# dual-relay-a-3.net
KiCad netlist of a schematic drawn in EAGLE
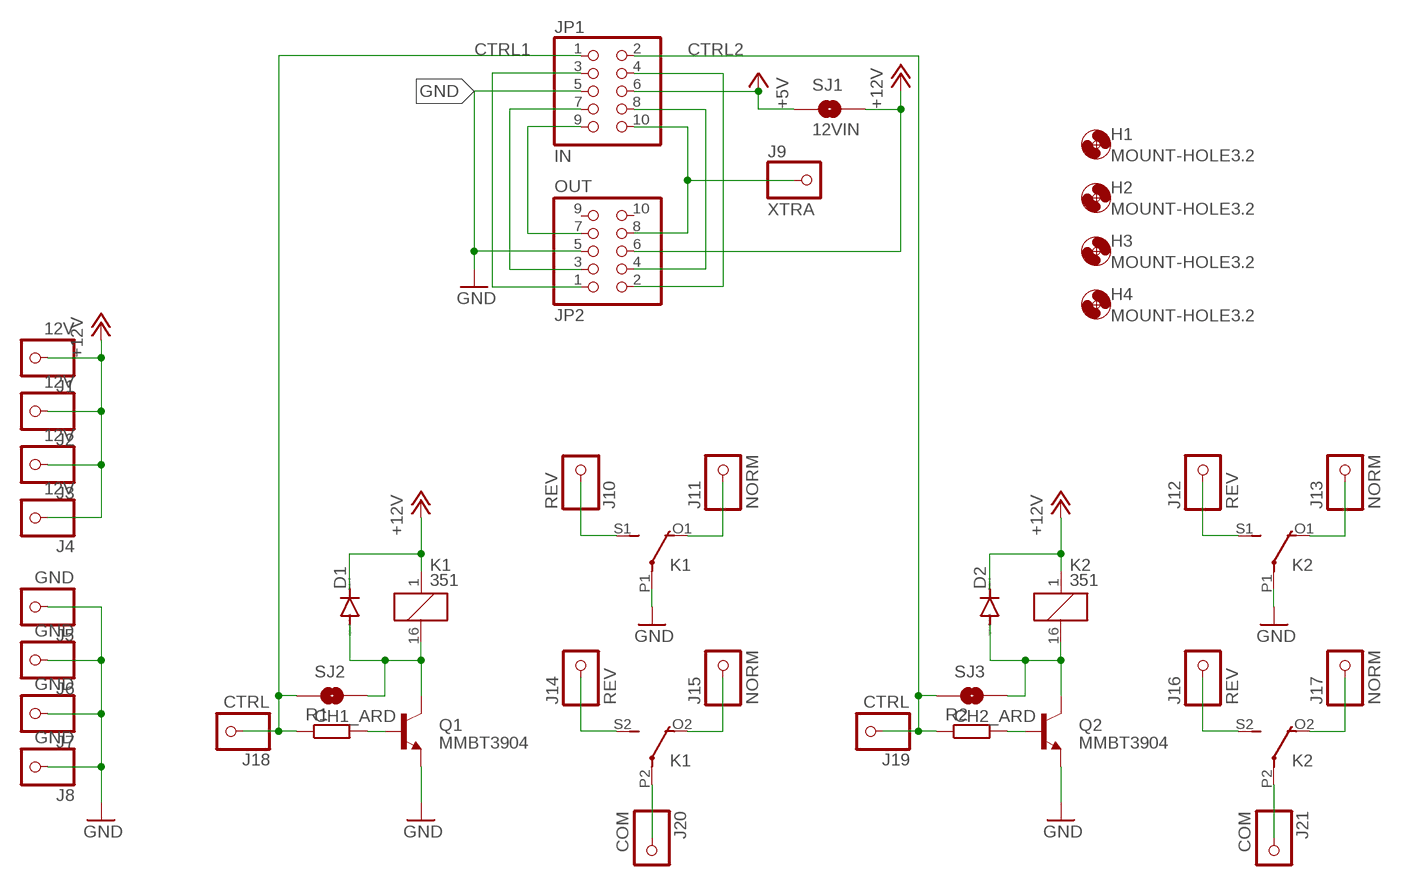
[diagram p0: schematic, sheet 1]

(export (version "E")
  (design (tool "Eeschema 10.0.6"))
  (components
    (comp (ref "D1")
      (value "DIODE-MINIMELF")
      (footprint "eagle-import:MINIMELF")
      (libsource (lib "eagle-import") (part "DIODE-MINIMELF"))
    )
    (comp (ref "D2")
      (value "DIODE-MINIMELF")
      (footprint "eagle-import:MINIMELF")
      (libsource (lib "eagle-import") (part "DIODE-MINIMELF"))
    )
    (comp (ref "H1")
      (value "MOUNT-HOLE3.2")
      (footprint "eagle-import:3,2")
      (libsource (lib "eagle-import") (part "MOUNT-HOLE3.2"))
    )
    (comp (ref "H2")
      (value "MOUNT-HOLE3.2")
      (footprint "eagle-import:3,2")
      (libsource (lib "eagle-import") (part "MOUNT-HOLE3.2"))
    )
    (comp (ref "H3")
      (value "MOUNT-HOLE3.2")
      (footprint "eagle-import:3,2")
      (libsource (lib "eagle-import") (part "MOUNT-HOLE3.2"))
    )
    (comp (ref "H4")
      (value "MOUNT-HOLE3.2")
      (footprint "eagle-import:3,2")
      (libsource (lib "eagle-import") (part "MOUNT-HOLE3.2"))
    )
    (comp (ref "J1")
      (value "12V")
      (footprint "eagle-import:LARGE-SOLDERPAD")
      (libsource (lib "eagle-import") (part "LARGE-SOLDERPAD"))
    )
    (comp (ref "J2")
      (value "12V")
      (footprint "eagle-import:LARGE-SOLDERPAD")
      (libsource (lib "eagle-import") (part "LARGE-SOLDERPAD"))
    )
    (comp (ref "J3")
      (value "12V")
      (footprint "eagle-import:LARGE-SOLDERPAD")
      (libsource (lib "eagle-import") (part "LARGE-SOLDERPAD"))
    )
    (comp (ref "J4")
      (value "12V")
      (footprint "eagle-import:LARGE-SOLDERPAD")
      (libsource (lib "eagle-import") (part "LARGE-SOLDERPAD"))
    )
    (comp (ref "J5")
      (value "GND")
      (footprint "eagle-import:LARGE-SOLDERPAD")
      (libsource (lib "eagle-import") (part "LARGE-SOLDERPAD"))
    )
    (comp (ref "J6")
      (value "GND")
      (footprint "eagle-import:LARGE-SOLDERPAD")
      (libsource (lib "eagle-import") (part "LARGE-SOLDERPAD"))
    )
    (comp (ref "J7")
      (value "GND")
      (footprint "eagle-import:LARGE-SOLDERPAD")
      (libsource (lib "eagle-import") (part "LARGE-SOLDERPAD"))
    )
    (comp (ref "J8")
      (value "GND")
      (footprint "eagle-import:LARGE-SOLDERPAD")
      (libsource (lib "eagle-import") (part "LARGE-SOLDERPAD"))
    )
    (comp (ref "J9")
      (value "XTRA")
      (footprint "eagle-import:LARGE-SOLDERPAD")
      (libsource (lib "eagle-import") (part "LARGE-SOLDERPAD"))
    )
    (comp (ref "J10")
      (value "REV")
      (footprint "eagle-import:LARGE-SOLDERPAD")
      (libsource (lib "eagle-import") (part "LARGE-SOLDERPAD"))
    )
    (comp (ref "J11")
      (value "NORM")
      (footprint "eagle-import:LARGE-SOLDERPAD")
      (libsource (lib "eagle-import") (part "LARGE-SOLDERPAD"))
    )
    (comp (ref "J12")
      (value "REV")
      (footprint "eagle-import:LARGE-SOLDERPAD")
      (libsource (lib "eagle-import") (part "LARGE-SOLDERPAD"))
    )
    (comp (ref "J13")
      (value "NORM")
      (footprint "eagle-import:LARGE-SOLDERPAD")
      (libsource (lib "eagle-import") (part "LARGE-SOLDERPAD"))
    )
    (comp (ref "J14")
      (value "REV")
      (footprint "eagle-import:LARGE-SOLDERPAD")
      (libsource (lib "eagle-import") (part "LARGE-SOLDERPAD"))
    )
    (comp (ref "J15")
      (value "NORM")
      (footprint "eagle-import:LARGE-SOLDERPAD")
      (libsource (lib "eagle-import") (part "LARGE-SOLDERPAD"))
    )
    (comp (ref "J16")
      (value "REV")
      (footprint "eagle-import:LARGE-SOLDERPAD")
      (libsource (lib "eagle-import") (part "LARGE-SOLDERPAD"))
    )
    (comp (ref "J17")
      (value "NORM")
      (footprint "eagle-import:LARGE-SOLDERPAD")
      (libsource (lib "eagle-import") (part "LARGE-SOLDERPAD"))
    )
    (comp (ref "J18")
      (value "CTRL")
      (footprint "eagle-import:LARGE-SOLDERPAD")
      (libsource (lib "eagle-import") (part "LARGE-SOLDERPAD"))
    )
    (comp (ref "J19")
      (value "CTRL")
      (footprint "eagle-import:LARGE-SOLDERPAD")
      (libsource (lib "eagle-import") (part "LARGE-SOLDERPAD"))
    )
    (comp (ref "J20")
      (value "COM")
      (footprint "eagle-import:LARGE-SOLDERPAD")
      (libsource (lib "eagle-import") (part "LARGE-SOLDERPAD"))
    )
    (comp (ref "J21")
      (value "COM")
      (footprint "eagle-import:LARGE-SOLDERPAD")
      (libsource (lib "eagle-import") (part "LARGE-SOLDERPAD"))
    )
    (comp (ref "JP1")
      (value "IN")
      (footprint "eagle-import:CON10M")
      (libsource (lib "eagle-import") (part "PINHD-2X5CN"))
    )
    (comp (ref "JP2")
      (value "OUT")
      (footprint "eagle-import:CON10M")
      (libsource (lib "eagle-import") (part "PINHD-2X5CN"))
    )
    (comp (ref "K1")
      (value "351")
      (footprint "eagle-import:351")
      (libsource (lib "eagle-import") (part "351"))
    )
    (comp (ref "K2")
      (value "351")
      (footprint "eagle-import:351")
      (libsource (lib "eagle-import") (part "351"))
    )
    (comp (ref "Q1")
      (value "MMBT3904")
      (footprint "eagle-import:SOT23")
      (libsource (lib "eagle-import") (part "NPN-23"))
    )
    (comp (ref "Q2")
      (value "MMBT3904")
      (footprint "eagle-import:SOT23")
      (libsource (lib "eagle-import") (part "NPN-23"))
    )
    (comp (ref "R1")
      (value "R-EU_R0805")
      (footprint "eagle-import:R0805")
      (libsource (lib "eagle-import") (part "R-EU_R0805"))
    )
    (comp (ref "R2")
      (value "R-EU_R0805")
      (footprint "eagle-import:R0805")
      (libsource (lib "eagle-import") (part "R-EU_R0805"))
    )
    (comp (ref "SJ1")
      (value "12VIN")
      (footprint "eagle-import:SJ_RND2")
      (libsource (lib "eagle-import") (part "SJRND2"))
    )
    (comp (ref "SJ2")
      (value "CH1_ARD")
      (footprint "eagle-import:SJ_RND2")
      (libsource (lib "eagle-import") (part "SJRND2"))
    )
    (comp (ref "SJ3")
      (value "CH2_ARD")
      (footprint "eagle-import:SJ_RND2")
      (libsource (lib "eagle-import") (part "SJRND2"))
    )
  )
  (nets
    (net (code "1") (name "+5V") (class "Default")
      (node (ref "JP1") (pin "6") (pinfunction "6_6") (pintype "passive"))
      (node (ref "SJ1") (pin "P$1") (pinfunction "1_P$1") (pintype "passive"))
    )
    (net (code "2") (name "+12V") (class "Default")
      (node (ref "D1") (pin "C") (pinfunction "C_C") (pintype "passive"))
      (node (ref "D2") (pin "C") (pinfunction "C_C") (pintype "passive"))
      (node (ref "J1") (pin "P$1") (pinfunction "1_P$1") (pintype "passive"))
      (node (ref "J2") (pin "P$1") (pinfunction "1_P$1") (pintype "passive"))
      (node (ref "J3") (pin "P$1") (pinfunction "1_P$1") (pintype "passive"))
      (node (ref "J4") (pin "P$1") (pinfunction "1_P$1") (pintype "passive"))
      (node (ref "JP2") (pin "6") (pinfunction "6_6") (pintype "passive"))
      (node (ref "K1") (pin "1") (pinfunction "1_1") (pintype "passive"))
      (node (ref "K2") (pin "1") (pinfunction "1_1") (pintype "passive"))
      (node (ref "SJ1") (pin "P$2") (pinfunction "2_P$2") (pintype "passive"))
    )
    (net (code "3") (name "/CTRL1") (class "Default")
      (node (ref "J18") (pin "P$1") (pinfunction "1_P$1") (pintype "passive"))
      (node (ref "JP1") (pin "1") (pinfunction "1_1") (pintype "passive"))
      (node (ref "R1") (pin "1") (pinfunction "1_1") (pintype "passive"))
      (node (ref "SJ2") (pin "P$1") (pinfunction "1_P$1") (pintype "passive"))
    )
    (net (code "4") (name "/CTRL2") (class "Default")
      (node (ref "J19") (pin "P$1") (pinfunction "1_P$1") (pintype "passive"))
      (node (ref "JP1") (pin "2") (pinfunction "2_2") (pintype "passive"))
      (node (ref "R2") (pin "1") (pinfunction "1_1") (pintype "passive"))
      (node (ref "SJ3") (pin "P$1") (pinfunction "1_P$1") (pintype "passive"))
    )
    (net (code "5") (name "GND") (class "Default")
      (node (ref "J5") (pin "P$1") (pinfunction "1_P$1") (pintype "passive"))
      (node (ref "J6") (pin "P$1") (pinfunction "1_P$1") (pintype "passive"))
      (node (ref "J7") (pin "P$1") (pinfunction "1_P$1") (pintype "passive"))
      (node (ref "J8") (pin "P$1") (pinfunction "1_P$1") (pintype "passive"))
      (node (ref "JP1") (pin "5") (pinfunction "5_5") (pintype "passive"))
      (node (ref "JP2") (pin "5") (pinfunction "5_5") (pintype "passive"))
      (node (ref "K1") (pin "P1") (pinfunction "P_P1") (pintype "passive"))
      (node (ref "K2") (pin "P1") (pinfunction "P_P1") (pintype "passive"))
      (node (ref "Q1") (pin "2") (pinfunction "E_2") (pintype "passive"))
      (node (ref "Q2") (pin "2") (pinfunction "E_2") (pintype "passive"))
    )
    (net (code "6") (name "Net-(J9-1)") (class "Default")
      (node (ref "J9") (pin "P$1") (pinfunction "1_P$1") (pintype "passive"))
      (node (ref "JP1") (pin "10") (pinfunction "10_10") (pintype "passive"))
      (node (ref "JP2") (pin "8") (pinfunction "8_8") (pintype "passive"))
    )
    (net (code "7") (name "Net-(J10-1)") (class "Default")
      (node (ref "J10") (pin "P$1") (pinfunction "1_P$1") (pintype "passive"))
      (node (ref "K1") (pin "S1") (pinfunction "S_S1") (pintype "passive"))
    )
    (net (code "8") (name "Net-(J11-1)") (class "Default")
      (node (ref "J11") (pin "P$1") (pinfunction "1_P$1") (pintype "passive"))
      (node (ref "K1") (pin "O1") (pinfunction "O_O1") (pintype "passive"))
    )
    (net (code "9") (name "Net-(J12-1)") (class "Default")
      (node (ref "J12") (pin "P$1") (pinfunction "1_P$1") (pintype "passive"))
      (node (ref "K2") (pin "S1") (pinfunction "S_S1") (pintype "passive"))
    )
    (net (code "10") (name "Net-(J13-1)") (class "Default")
      (node (ref "J13") (pin "P$1") (pinfunction "1_P$1") (pintype "passive"))
      (node (ref "K2") (pin "O1") (pinfunction "O_O1") (pintype "passive"))
    )
    (net (code "11") (name "Net-(J14-1)") (class "Default")
      (node (ref "J14") (pin "P$1") (pinfunction "1_P$1") (pintype "passive"))
      (node (ref "K1") (pin "S2") (pinfunction "S_S2") (pintype "passive"))
    )
    (net (code "12") (name "Net-(J15-1)") (class "Default")
      (node (ref "J15") (pin "P$1") (pinfunction "1_P$1") (pintype "passive"))
      (node (ref "K1") (pin "O2") (pinfunction "O_O2") (pintype "passive"))
    )
    (net (code "13") (name "Net-(J16-1)") (class "Default")
      (node (ref "J16") (pin "P$1") (pinfunction "1_P$1") (pintype "passive"))
      (node (ref "K2") (pin "S2") (pinfunction "S_S2") (pintype "passive"))
    )
    (net (code "14") (name "Net-(J17-1)") (class "Default")
      (node (ref "J17") (pin "P$1") (pinfunction "1_P$1") (pintype "passive"))
      (node (ref "K2") (pin "O2") (pinfunction "O_O2") (pintype "passive"))
    )
    (net (code "15") (name "Net-(J20-1)") (class "Default")
      (node (ref "J20") (pin "P$1") (pinfunction "1_P$1") (pintype "passive"))
      (node (ref "K1") (pin "P2") (pinfunction "P_P2") (pintype "passive"))
    )
    (net (code "16") (name "Net-(J21-1)") (class "Default")
      (node (ref "J21") (pin "P$1") (pinfunction "1_P$1") (pintype "passive"))
      (node (ref "K2") (pin "P2") (pinfunction "P_P2") (pintype "passive"))
    )
    (net (code "17") (name "Net-(JP1-Pad3)") (class "Default")
      (node (ref "JP1") (pin "3") (pinfunction "3_3") (pintype "passive"))
      (node (ref "JP2") (pin "1") (pinfunction "1_1") (pintype "passive"))
    )
    (net (code "18") (name "Net-(JP1-Pad4)") (class "Default")
      (node (ref "JP1") (pin "4") (pinfunction "4_4") (pintype "passive"))
      (node (ref "JP2") (pin "2") (pinfunction "2_2") (pintype "passive"))
    )
    (net (code "19") (name "Net-(JP1-Pad7)") (class "Default")
      (node (ref "JP1") (pin "7") (pinfunction "7_7") (pintype "passive"))
      (node (ref "JP2") (pin "3") (pinfunction "3_3") (pintype "passive"))
    )
    (net (code "20") (name "Net-(JP1-Pad8)") (class "Default")
      (node (ref "JP1") (pin "8") (pinfunction "8_8") (pintype "passive"))
      (node (ref "JP2") (pin "4") (pinfunction "4_4") (pintype "passive"))
    )
    (net (code "21") (name "Net-(JP1-Pad9)") (class "Default")
      (node (ref "JP1") (pin "9") (pinfunction "9_9") (pintype "passive"))
      (node (ref "JP2") (pin "7") (pinfunction "7_7") (pintype "passive"))
    )
    (net (code "22") (name "Net-(K1A-2)") (class "Default")
      (node (ref "D1") (pin "A") (pinfunction "A_A") (pintype "passive"))
      (node (ref "K1") (pin "16") (pinfunction "2_16") (pintype "passive"))
      (node (ref "Q1") (pin "3") (pinfunction "C_3") (pintype "passive"))
      (node (ref "SJ2") (pin "P$2") (pinfunction "2_P$2") (pintype "passive"))
    )
    (net (code "23") (name "Net-(K2A-2)") (class "Default")
      (node (ref "D2") (pin "A") (pinfunction "A_A") (pintype "passive"))
      (node (ref "K2") (pin "16") (pinfunction "2_16") (pintype "passive"))
      (node (ref "Q2") (pin "3") (pinfunction "C_3") (pintype "passive"))
      (node (ref "SJ3") (pin "P$2") (pinfunction "2_P$2") (pintype "passive"))
    )
    (net (code "24") (name "Net-(Q1-B)") (class "Default")
      (node (ref "Q1") (pin "1") (pinfunction "B_1") (pintype "passive"))
      (node (ref "R1") (pin "2") (pinfunction "2_2") (pintype "passive"))
    )
    (net (code "25") (name "Net-(Q2-B)") (class "Default")
      (node (ref "Q2") (pin "1") (pinfunction "B_1") (pintype "passive"))
      (node (ref "R2") (pin "2") (pinfunction "2_2") (pintype "passive"))
    )
    (net (code "26") (name "unconnected-(JP2-Pad9)") (class "Default")
      (node (ref "JP2") (pin "9") (pinfunction "9_9") (pintype "passive"))
    )
    (net (code "27") (name "unconnected-(JP2-Pad10)") (class "Default")
      (node (ref "JP2") (pin "10") (pinfunction "10_10") (pintype "passive"))
    )
  )
)
